# microcontroller.net
KiCad netlist of a schematic drawn in Altium Designer
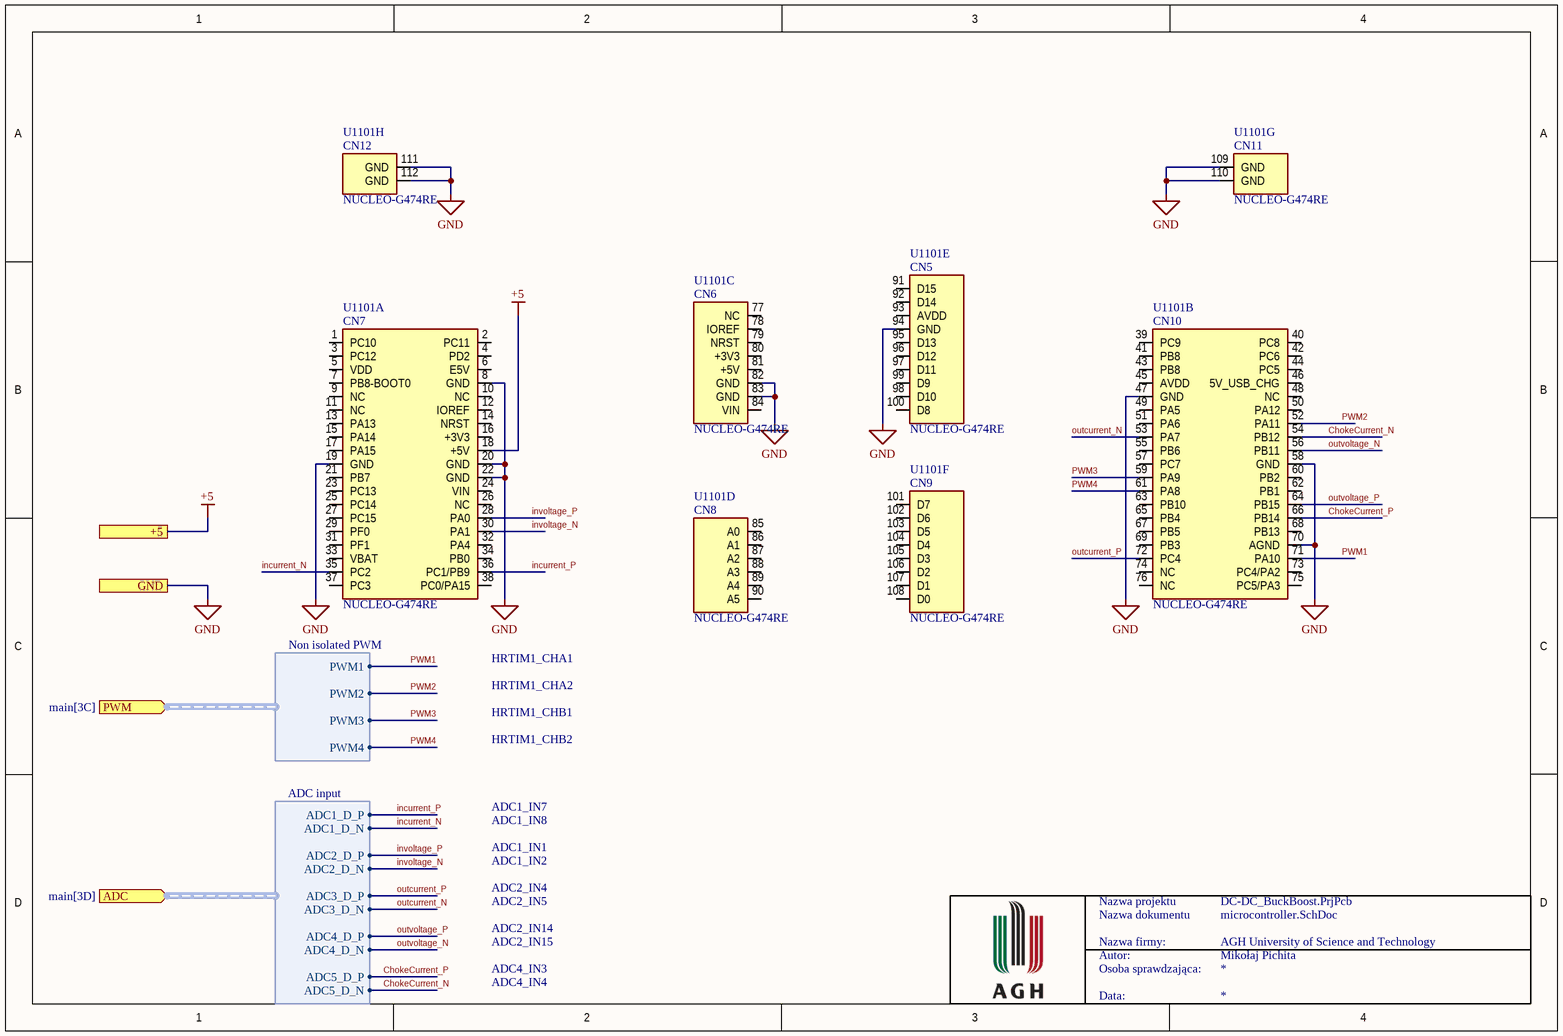
[diagram p0: microcontroller.SchDoc]

(export (version "E")
  (design (tool "Eeschema 10.0.6"))
  (components
    (comp (ref "U1101")
      (value "NUCLEO-G474RE")
      (footprint "G474RE")
      (libsource (lib "Integrated_Library") (part "NUCLEO-G474RE"))
    )
  )
  (nets
    (net (code "6") (name "+5") (class "Default")
      (node (ref "U1101") (pin "18") (pinfunction "+5V_18") (pintype "passive"))
    )
    (net (code "7") (name "/ChokeCurrent_N") (class "Default")
      (node (ref "U1101") (pin "54") (pinfunction "PB12_54") (pintype "passive"))
    )
    (net (code "8") (name "/ChokeCurrent_P") (class "Default")
      (node (ref "U1101") (pin "66") (pinfunction "PB14_66") (pintype "passive"))
    )
    (net (code "9") (name "/PWM1") (class "Default")
      (node (ref "U1101") (pin "71") (pinfunction "PA10_71") (pintype "passive"))
    )
    (net (code "10") (name "/PWM2") (class "Default")
      (node (ref "U1101") (pin "52") (pinfunction "PA11_52") (pintype "passive"))
    )
    (net (code "11") (name "/PWM3") (class "Default")
      (node (ref "U1101") (pin "59") (pinfunction "PA9_59") (pintype "passive"))
    )
    (net (code "12") (name "/PWM4") (class "Default")
      (node (ref "U1101") (pin "61") (pinfunction "PA8_61") (pintype "passive"))
    )
    (net (code "13") (name "/incurrent_N") (class "Default")
      (node (ref "U1101") (pin "35") (pinfunction "PC2_35") (pintype "passive"))
    )
    (net (code "14") (name "/incurrent_P") (class "Default")
      (node (ref "U1101") (pin "36") (pinfunction "PC1/PB9_36") (pintype "passive"))
    )
    (net (code "15") (name "/involtage_N") (class "Default")
      (node (ref "U1101") (pin "30") (pinfunction "PA1_30") (pintype "passive"))
    )
    (net (code "16") (name "/involtage_P") (class "Default")
      (node (ref "U1101") (pin "28") (pinfunction "PA0_28") (pintype "passive"))
    )
    (net (code "17") (name "/outcurrent_N") (class "Default")
      (node (ref "U1101") (pin "53") (pinfunction "PA7_53") (pintype "passive"))
    )
    (net (code "18") (name "/outcurrent_P") (class "Default")
      (node (ref "U1101") (pin "72") (pinfunction "PC4_72") (pintype "passive"))
    )
    (net (code "19") (name "/outvoltage_N") (class "Default")
      (node (ref "U1101") (pin "56") (pinfunction "PB11_56") (pintype "passive"))
    )
    (net (code "20") (name "/outvoltage_P") (class "Default")
      (node (ref "U1101") (pin "64") (pinfunction "PB15_64") (pintype "passive"))
    )
    (net (code "23") (name "GND") (class "Default")
      (node (ref "U1101") (pin "109") (pinfunction "GND_109") (pintype "passive"))
      (node (ref "U1101") (pin "110") (pinfunction "GND_110") (pintype "passive"))
      (node (ref "U1101") (pin "111") (pinfunction "GND_111") (pintype "passive"))
      (node (ref "U1101") (pin "112") (pinfunction "GND_112") (pintype "passive"))
      (node (ref "U1101") (pin "19") (pinfunction "GND_19") (pintype "passive"))
      (node (ref "U1101") (pin "20") (pinfunction "GND_20") (pintype "passive"))
      (node (ref "U1101") (pin "22") (pinfunction "GND_22") (pintype "passive"))
      (node (ref "U1101") (pin "47") (pinfunction "GND_47") (pintype "passive"))
      (node (ref "U1101") (pin "58") (pinfunction "GND_58") (pintype "passive"))
      (node (ref "U1101") (pin "70") (pinfunction "AGND_70") (pintype "passive"))
      (node (ref "U1101") (pin "8") (pinfunction "GND_8") (pintype "passive"))
      (node (ref "U1101") (pin "82") (pinfunction "GND_82") (pintype "passive"))
      (node (ref "U1101") (pin "83") (pinfunction "GND_83") (pintype "passive"))
      (node (ref "U1101") (pin "94") (pinfunction "GND_94") (pintype "passive"))
    )
    (net (code "24") (name "unconnected-(U1101A-+3V3-Pad16)") (class "Default")
      (node (ref "U1101") (pin "16") (pinfunction "+3V3_16") (pintype "passive"))
    )
    (net (code "25") (name "unconnected-(U1101A-E5V-Pad6)") (class "Default")
      (node (ref "U1101") (pin "6") (pinfunction "E5V_6") (pintype "passive"))
    )
    (net (code "26") (name "unconnected-(U1101A-IOREF-Pad12)") (class "Default")
      (node (ref "U1101") (pin "12") (pinfunction "IOREF_12") (pintype "passive"))
    )
    (net (code "27") (name "unconnected-(U1101A-NC-Pad9)") (class "Default")
      (node (ref "U1101") (pin "9") (pinfunction "NC_9") (pintype "passive"))
    )
    (net (code "28") (name "unconnected-(U1101A-NC-Pad10)") (class "Default")
      (node (ref "U1101") (pin "10") (pinfunction "NC_10") (pintype "passive"))
    )
    (net (code "29") (name "unconnected-(U1101A-NC-Pad11)") (class "Default")
      (node (ref "U1101") (pin "11") (pinfunction "NC_11") (pintype "passive"))
    )
    (net (code "30") (name "unconnected-(U1101A-NC-Pad26)") (class "Default")
      (node (ref "U1101") (pin "26") (pinfunction "NC_26") (pintype "passive"))
    )
    (net (code "31") (name "unconnected-(U1101A-NRST-Pad14)") (class "Default")
      (node (ref "U1101") (pin "14") (pinfunction "NRST_14") (pintype "passive"))
    )
    (net (code "32") (name "unconnected-(U1101A-PA4-Pad32)") (class "Default")
      (node (ref "U1101") (pin "32") (pinfunction "PA4_32") (pintype "passive"))
    )
    (net (code "33") (name "unconnected-(U1101A-PA13-Pad13)") (class "Default")
      (node (ref "U1101") (pin "13") (pinfunction "PA13_13") (pintype "passive"))
    )
    (net (code "34") (name "unconnected-(U1101A-PA14-Pad15)") (class "Default")
      (node (ref "U1101") (pin "15") (pinfunction "PA14_15") (pintype "passive"))
    )
    (net (code "35") (name "unconnected-(U1101A-PA15-Pad17)") (class "Default")
      (node (ref "U1101") (pin "17") (pinfunction "PA15_17") (pintype "passive"))
    )
    (net (code "36") (name "unconnected-(U1101A-PB0-Pad34)") (class "Default")
      (node (ref "U1101") (pin "34") (pinfunction "PB0_34") (pintype "passive"))
    )
    (net (code "37") (name "unconnected-(U1101A-PB7-Pad21)") (class "Default")
      (node (ref "U1101") (pin "21") (pinfunction "PB7_21") (pintype "passive"))
    )
    (net (code "38") (name "unconnected-(U1101A-PB8-BOOT0-Pad7)") (class "Default")
      (node (ref "U1101") (pin "7") (pinfunction "PB8-BOOT0_7") (pintype "passive"))
    )
    (net (code "39") (name "unconnected-(U1101A-PC0{slash}PA15-Pad38)") (class "Default")
      (node (ref "U1101") (pin "38") (pinfunction "PC0/PA15_38") (pintype "passive"))
    )
    (net (code "40") (name "unconnected-(U1101A-PC3-Pad37)") (class "Default")
      (node (ref "U1101") (pin "37") (pinfunction "PC3_37") (pintype "passive"))
    )
    (net (code "41") (name "unconnected-(U1101A-PC10-Pad1)") (class "Default")
      (node (ref "U1101") (pin "1") (pinfunction "PC10_1") (pintype "passive"))
    )
    (net (code "42") (name "unconnected-(U1101A-PC11-Pad2)") (class "Default")
      (node (ref "U1101") (pin "2") (pinfunction "PC11_2") (pintype "passive"))
    )
    (net (code "43") (name "unconnected-(U1101A-PC12-Pad3)") (class "Default")
      (node (ref "U1101") (pin "3") (pinfunction "PC12_3") (pintype "passive"))
    )
    (net (code "44") (name "unconnected-(U1101A-PC13-Pad23)") (class "Default")
      (node (ref "U1101") (pin "23") (pinfunction "PC13_23") (pintype "passive"))
    )
    (net (code "45") (name "unconnected-(U1101A-PC14-Pad25)") (class "Default")
      (node (ref "U1101") (pin "25") (pinfunction "PC14_25") (pintype "passive"))
    )
    (net (code "46") (name "unconnected-(U1101A-PC15-Pad27)") (class "Default")
      (node (ref "U1101") (pin "27") (pinfunction "PC15_27") (pintype "passive"))
    )
    (net (code "47") (name "unconnected-(U1101A-PD2-Pad4)") (class "Default")
      (node (ref "U1101") (pin "4") (pinfunction "PD2_4") (pintype "passive"))
    )
    (net (code "48") (name "unconnected-(U1101A-PF0-Pad29)") (class "Default")
      (node (ref "U1101") (pin "29") (pinfunction "PF0_29") (pintype "passive"))
    )
    (net (code "49") (name "unconnected-(U1101A-PF1-Pad31)") (class "Default")
      (node (ref "U1101") (pin "31") (pinfunction "PF1_31") (pintype "passive"))
    )
    (net (code "50") (name "unconnected-(U1101A-VBAT-Pad33)") (class "Default")
      (node (ref "U1101") (pin "33") (pinfunction "VBAT_33") (pintype "passive"))
    )
    (net (code "51") (name "unconnected-(U1101A-VDD-Pad5)") (class "Default")
      (node (ref "U1101") (pin "5") (pinfunction "VDD_5") (pintype "passive"))
    )
    (net (code "52") (name "unconnected-(U1101A-VIN-Pad24)") (class "Default")
      (node (ref "U1101") (pin "24") (pinfunction "VIN_24") (pintype "passive"))
    )
    (net (code "53") (name "unconnected-(U1101B-5V_USB_CHG-Pad46)") (class "Default")
      (node (ref "U1101") (pin "46") (pinfunction "5V_USB_CHG_46") (pintype "passive"))
    )
    (net (code "54") (name "unconnected-(U1101B-AVDD-Pad45)") (class "Default")
      (node (ref "U1101") (pin "45") (pinfunction "AVDD_45") (pintype "passive"))
    )
    (net (code "55") (name "unconnected-(U1101B-NC-Pad48)") (class "Default")
      (node (ref "U1101") (pin "48") (pinfunction "NC_48") (pintype "passive"))
    )
    (net (code "56") (name "unconnected-(U1101B-NC-Pad74)") (class "Default")
      (node (ref "U1101") (pin "74") (pinfunction "NC_74") (pintype "passive"))
    )
    (net (code "57") (name "unconnected-(U1101B-NC-Pad76)") (class "Default")
      (node (ref "U1101") (pin "76") (pinfunction "NC_76") (pintype "passive"))
    )
    (net (code "58") (name "unconnected-(U1101B-PA5-Pad49)") (class "Default")
      (node (ref "U1101") (pin "49") (pinfunction "PA5_49") (pintype "passive"))
    )
    (net (code "59") (name "unconnected-(U1101B-PA6-Pad51)") (class "Default")
      (node (ref "U1101") (pin "51") (pinfunction "PA6_51") (pintype "passive"))
    )
    (net (code "60") (name "unconnected-(U1101B-PA12-Pad50)") (class "Default")
      (node (ref "U1101") (pin "50") (pinfunction "PA12_50") (pintype "passive"))
    )
    (net (code "61") (name "unconnected-(U1101B-PB1-Pad62)") (class "Default")
      (node (ref "U1101") (pin "62") (pinfunction "PB1_62") (pintype "passive"))
    )
    (net (code "62") (name "unconnected-(U1101B-PB2-Pad60)") (class "Default")
      (node (ref "U1101") (pin "60") (pinfunction "PB2_60") (pintype "passive"))
    )
    (net (code "63") (name "unconnected-(U1101B-PB3-Pad69)") (class "Default")
      (node (ref "U1101") (pin "69") (pinfunction "PB3_69") (pintype "passive"))
    )
    (net (code "64") (name "unconnected-(U1101B-PB4-Pad65)") (class "Default")
      (node (ref "U1101") (pin "65") (pinfunction "PB4_65") (pintype "passive"))
    )
    (net (code "65") (name "unconnected-(U1101B-PB5-Pad67)") (class "Default")
      (node (ref "U1101") (pin "67") (pinfunction "PB5_67") (pintype "passive"))
    )
    (net (code "66") (name "unconnected-(U1101B-PB6-Pad55)") (class "Default")
      (node (ref "U1101") (pin "55") (pinfunction "PB6_55") (pintype "passive"))
    )
    (net (code "67") (name "unconnected-(U1101B-PB8-Pad41)") (class "Default")
      (node (ref "U1101") (pin "41") (pinfunction "PB8_41") (pintype "passive"))
    )
    (net (code "68") (name "unconnected-(U1101B-PB8-Pad43)") (class "Default")
      (node (ref "U1101") (pin "43") (pinfunction "PB8_43") (pintype "passive"))
    )
    (net (code "69") (name "unconnected-(U1101B-PB10-Pad63)") (class "Default")
      (node (ref "U1101") (pin "63") (pinfunction "PB10_63") (pintype "passive"))
    )
    (net (code "70") (name "unconnected-(U1101B-PB13-Pad68)") (class "Default")
      (node (ref "U1101") (pin "68") (pinfunction "PB13_68") (pintype "passive"))
    )
    (net (code "71") (name "unconnected-(U1101B-PC4{slash}PA2-Pad73)") (class "Default")
      (node (ref "U1101") (pin "73") (pinfunction "PC4/PA2_73") (pintype "passive"))
    )
    (net (code "72") (name "unconnected-(U1101B-PC5-Pad44)") (class "Default")
      (node (ref "U1101") (pin "44") (pinfunction "PC5_44") (pintype "passive"))
    )
    (net (code "73") (name "unconnected-(U1101B-PC5{slash}PA3-Pad75)") (class "Default")
      (node (ref "U1101") (pin "75") (pinfunction "PC5/PA3_75") (pintype "passive"))
    )
    (net (code "74") (name "unconnected-(U1101B-PC6-Pad42)") (class "Default")
      (node (ref "U1101") (pin "42") (pinfunction "PC6_42") (pintype "passive"))
    )
    (net (code "75") (name "unconnected-(U1101B-PC7-Pad57)") (class "Default")
      (node (ref "U1101") (pin "57") (pinfunction "PC7_57") (pintype "passive"))
    )
    (net (code "76") (name "unconnected-(U1101B-PC8-Pad40)") (class "Default")
      (node (ref "U1101") (pin "40") (pinfunction "PC8_40") (pintype "passive"))
    )
    (net (code "77") (name "unconnected-(U1101B-PC9-Pad39)") (class "Default")
      (node (ref "U1101") (pin "39") (pinfunction "PC9_39") (pintype "passive"))
    )
    (net (code "78") (name "unconnected-(U1101C-+3V3-Pad80)") (class "Default")
      (node (ref "U1101") (pin "80") (pinfunction "+3V3_80") (pintype "passive"))
    )
    (net (code "79") (name "unconnected-(U1101C-+5V-Pad81)") (class "Default")
      (node (ref "U1101") (pin "81") (pinfunction "+5V_81") (pintype "passive"))
    )
    (net (code "80") (name "unconnected-(U1101C-IOREF-Pad78)") (class "Default")
      (node (ref "U1101") (pin "78") (pinfunction "IOREF_78") (pintype "passive"))
    )
    (net (code "81") (name "unconnected-(U1101C-NC-Pad77)") (class "Default")
      (node (ref "U1101") (pin "77") (pinfunction "NC_77") (pintype "passive"))
    )
    (net (code "82") (name "unconnected-(U1101C-NRST-Pad79)") (class "Default")
      (node (ref "U1101") (pin "79") (pinfunction "NRST_79") (pintype "passive"))
    )
    (net (code "83") (name "unconnected-(U1101C-VIN-Pad84)") (class "Default")
      (node (ref "U1101") (pin "84") (pinfunction "VIN_84") (pintype "passive"))
    )
    (net (code "84") (name "unconnected-(U1101D-A0-Pad85)") (class "Default")
      (node (ref "U1101") (pin "85") (pinfunction "A0_85") (pintype "passive"))
    )
    (net (code "85") (name "unconnected-(U1101D-A1-Pad86)") (class "Default")
      (node (ref "U1101") (pin "86") (pinfunction "A1_86") (pintype "passive"))
    )
    (net (code "86") (name "unconnected-(U1101D-A2-Pad87)") (class "Default")
      (node (ref "U1101") (pin "87") (pinfunction "A2_87") (pintype "passive"))
    )
    (net (code "87") (name "unconnected-(U1101D-A3-Pad88)") (class "Default")
      (node (ref "U1101") (pin "88") (pinfunction "A3_88") (pintype "passive"))
    )
    (net (code "88") (name "unconnected-(U1101D-A4-Pad89)") (class "Default")
      (node (ref "U1101") (pin "89") (pinfunction "A4_89") (pintype "passive"))
    )
    (net (code "89") (name "unconnected-(U1101D-A5-Pad90)") (class "Default")
      (node (ref "U1101") (pin "90") (pinfunction "A5_90") (pintype "passive"))
    )
    (net (code "90") (name "unconnected-(U1101E-AVDD-Pad93)") (class "Default")
      (node (ref "U1101") (pin "93") (pinfunction "AVDD_93") (pintype "passive"))
    )
    (net (code "91") (name "unconnected-(U1101E-D8-Pad100)") (class "Default")
      (node (ref "U1101") (pin "100") (pinfunction "D8_100") (pintype "passive"))
    )
    (net (code "92") (name "unconnected-(U1101E-D9-Pad99)") (class "Default")
      (node (ref "U1101") (pin "99") (pinfunction "D9_99") (pintype "passive"))
    )
    (net (code "93") (name "unconnected-(U1101E-D10-Pad98)") (class "Default")
      (node (ref "U1101") (pin "98") (pinfunction "D10_98") (pintype "passive"))
    )
    (net (code "94") (name "unconnected-(U1101E-D11-Pad97)") (class "Default")
      (node (ref "U1101") (pin "97") (pinfunction "D11_97") (pintype "passive"))
    )
    (net (code "95") (name "unconnected-(U1101E-D12-Pad96)") (class "Default")
      (node (ref "U1101") (pin "96") (pinfunction "D12_96") (pintype "passive"))
    )
    (net (code "96") (name "unconnected-(U1101E-D13-Pad95)") (class "Default")
      (node (ref "U1101") (pin "95") (pinfunction "D13_95") (pintype "passive"))
    )
    (net (code "97") (name "unconnected-(U1101E-D14-Pad92)") (class "Default")
      (node (ref "U1101") (pin "92") (pinfunction "D14_92") (pintype "passive"))
    )
    (net (code "98") (name "unconnected-(U1101E-D15-Pad91)") (class "Default")
      (node (ref "U1101") (pin "91") (pinfunction "D15_91") (pintype "passive"))
    )
    (net (code "99") (name "unconnected-(U1101F-D0-Pad108)") (class "Default")
      (node (ref "U1101") (pin "108") (pinfunction "D0_108") (pintype "passive"))
    )
    (net (code "100") (name "unconnected-(U1101F-D1-Pad107)") (class "Default")
      (node (ref "U1101") (pin "107") (pinfunction "D1_107") (pintype "passive"))
    )
    (net (code "101") (name "unconnected-(U1101F-D2-Pad106)") (class "Default")
      (node (ref "U1101") (pin "106") (pinfunction "D2_106") (pintype "passive"))
    )
    (net (code "102") (name "unconnected-(U1101F-D3-Pad105)") (class "Default")
      (node (ref "U1101") (pin "105") (pinfunction "D3_105") (pintype "passive"))
    )
    (net (code "103") (name "unconnected-(U1101F-D4-Pad104)") (class "Default")
      (node (ref "U1101") (pin "104") (pinfunction "D4_104") (pintype "passive"))
    )
    (net (code "104") (name "unconnected-(U1101F-D5-Pad103)") (class "Default")
      (node (ref "U1101") (pin "103") (pinfunction "D5_103") (pintype "passive"))
    )
    (net (code "105") (name "unconnected-(U1101F-D6-Pad102)") (class "Default")
      (node (ref "U1101") (pin "102") (pinfunction "D6_102") (pintype "passive"))
    )
    (net (code "106") (name "unconnected-(U1101F-D7-Pad101)") (class "Default")
      (node (ref "U1101") (pin "101") (pinfunction "D7_101") (pintype "passive"))
    )
  )
)
